# Level_Matching.net
KiCad netlist of a schematic drawn in Altium Designer
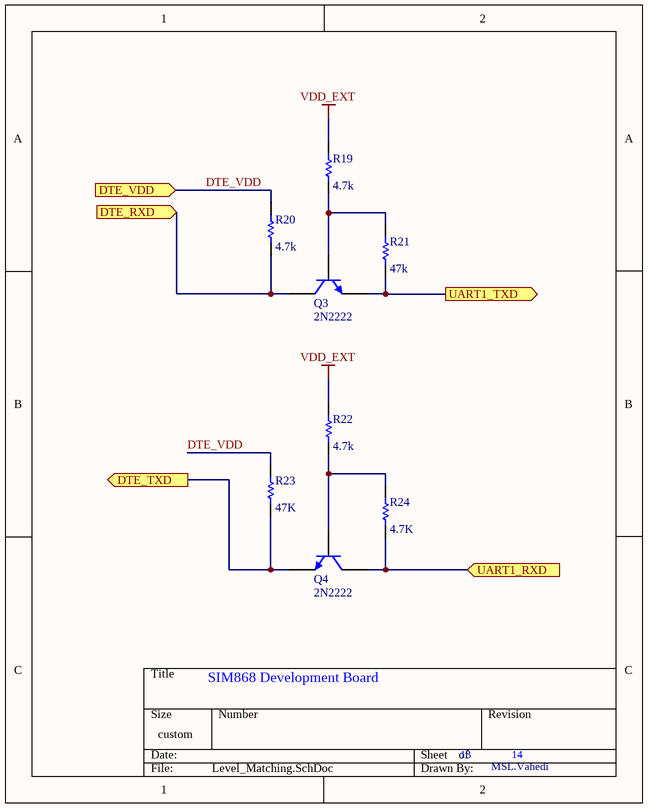
[diagram p0: Level_Matching.SchDoc]

(export (version "E")
  (design (tool "Eeschema 10.0.6"))
  (components
    (comp (ref "Q3")
      (value "2N2222")
      (footprint "SOT-23")
      (description "NPN General Purpose Amplifier")
      (fields (field (name "PUBLISHER") "Altium Limited"))
      (libsource (lib "Miscellaneous Devices") (part "2N3904"))
    )
    (comp (ref "Q4")
      (value "2N2222")
      (footprint "SOT-23")
      (description "NPN General Purpose Amplifier")
      (fields (field (name "PUBLISHER") "Altium Limited"))
      (libsource (lib "Miscellaneous Devices") (part "2N3904"))
    )
    (comp (ref "R19")
      (value "4.7k")
      (footprint "RES0805")
      (description "Resistor")
      (fields (field (name "PUBLISHER") "Altium Limited"))
      (libsource (lib "Miscellaneous Devices") (part "Res1"))
    )
    (comp (ref "R20")
      (value "4.7k")
      (footprint "RES0805")
      (description "Resistor")
      (fields (field (name "PUBLISHER") "Altium Limited"))
      (libsource (lib "Miscellaneous Devices") (part "Res1"))
    )
    (comp (ref "R21")
      (value "47k")
      (footprint "RES0805")
      (description "Resistor")
      (fields (field (name "PUBLISHER") "Altium Limited"))
      (libsource (lib "Miscellaneous Devices") (part "Res1"))
    )
    (comp (ref "R22")
      (value "4.7k")
      (footprint "RES0805")
      (description "Resistor")
      (fields (field (name "PUBLISHER") "Altium Limited"))
      (libsource (lib "Miscellaneous Devices") (part "Res1"))
    )
    (comp (ref "R23")
      (value "47K")
      (footprint "RES0805")
      (description "Resistor")
      (fields (field (name "PUBLISHER") "Altium Limited"))
      (libsource (lib "Miscellaneous Devices") (part "Res1"))
    )
    (comp (ref "R24")
      (value "4.7K")
      (footprint "RES0805")
      (description "Resistor")
      (fields (field (name "PUBLISHER") "Altium Limited"))
      (libsource (lib "Miscellaneous Devices") (part "Res1"))
    )
  )
  (nets
    (net (code "1") (name "/DTE_RXD") (class "Default")
      (node (ref "Q3") (pin "3") (pinfunction "C_3") (pintype "passive"))
      (node (ref "R20") (pin "2") (pinfunction "2_2") (pintype "passive"))
    )
    (net (code "2") (name "/DTE_TXD") (class "Default")
      (node (ref "Q4") (pin "1") (pinfunction "E_1") (pintype "passive"))
      (node (ref "R23") (pin "2") (pinfunction "2_2") (pintype "passive"))
    )
    (net (code "3") (name "/DTE_VDD") (class "Default")
      (node (ref "R20") (pin "1") (pinfunction "1_1") (pintype "passive"))
      (node (ref "R23") (pin "1") (pinfunction "1_1") (pintype "passive"))
    )
    (net (code "4") (name "/UART1_RXD") (class "Default")
      (node (ref "Q4") (pin "3") (pinfunction "C_3") (pintype "passive"))
      (node (ref "R24") (pin "2") (pinfunction "2_2") (pintype "passive"))
    )
    (net (code "5") (name "/UART1_TXD") (class "Default")
      (node (ref "Q3") (pin "1") (pinfunction "E_1") (pintype "passive"))
      (node (ref "R21") (pin "2") (pinfunction "2_2") (pintype "passive"))
    )
    (net (code "6") (name "Net-(Q3-B)") (class "Default")
      (node (ref "Q3") (pin "2") (pinfunction "B_2") (pintype "passive"))
      (node (ref "R19") (pin "2") (pinfunction "2_2") (pintype "passive"))
      (node (ref "R21") (pin "1") (pinfunction "1_1") (pintype "passive"))
    )
    (net (code "7") (name "Net-(Q4-B)") (class "Default")
      (node (ref "Q4") (pin "2") (pinfunction "B_2") (pintype "passive"))
      (node (ref "R22") (pin "2") (pinfunction "2_2") (pintype "passive"))
      (node (ref "R24") (pin "1") (pinfunction "1_1") (pintype "passive"))
    )
    (net (code "8") (name "VDD_EXT") (class "Default")
      (node (ref "R19") (pin "1") (pinfunction "1_1") (pintype "passive"))
      (node (ref "R22") (pin "1") (pinfunction "1_1") (pintype "passive"))
    )
  )
)
